# Gas_Sampler-5V_Buck.net
KiCad netlist of a schematic drawn in Altium Designer
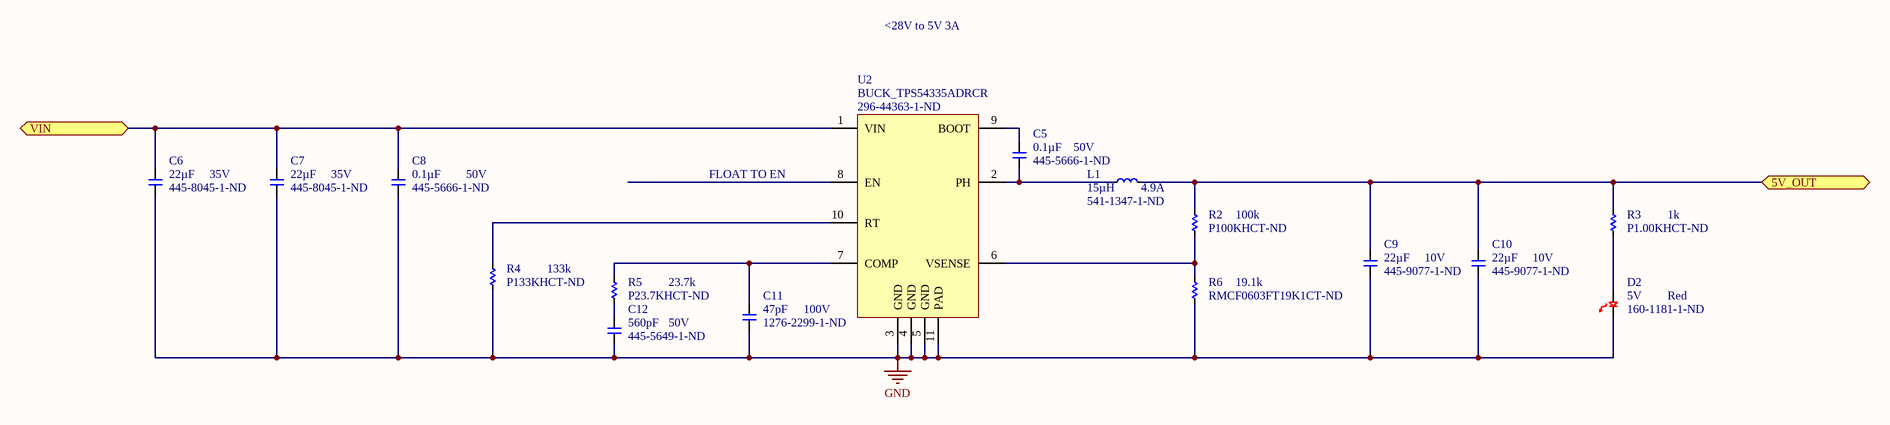
[diagram p0: Gas_Sampler-5V_Buck.SchDoc]

(export (version "E")
  (design (tool "Eeschema 10.0.6"))
  (components
    (comp (ref "C5")
      (value "0.1µF")
      (footprint "C0603")
      (description "CAP CER 0.1UF 50V 10% X7R 0603")
      (fields
        (field (name "MANUFACTURER") "TDK Corporation")
        (field (name "MANUFACTURER PART NUMBER") "CGA3E2X7R1H104K080AA")
        (field (name "VOLTAGE - RATED") "50V")
        (field (name "SUPPLIER PART NUMBER 1") "445-5666-1-ND")
      )
      (libsource (lib "capacitor") (part "CAP_CER_0603_0.1UF_50V_10%_X7R"))
    )
    (comp (ref "C6")
      (value "22µF")
      (footprint "C1206")
      (description "CAP CER 22UF 35V X5R 1206")
      (fields
        (field (name "MANUFACTURER") "TDK Corporation")
        (field (name "MANUFACTURER PART NUMBER") "C3216X5R1V226M160AC")
        (field (name "VOLTAGE - RATED") "35V")
        (field (name "SUPPLIER PART NUMBER 1") "445-8045-1-ND")
      )
      (libsource (lib "capacitor") (part "CAP_CER_1206_22UF_35V_20%_X5R"))
    )
    (comp (ref "C7")
      (value "22µF")
      (footprint "C1206")
      (description "CAP CER 22UF 35V X5R 1206")
      (fields
        (field (name "MANUFACTURER") "TDK Corporation")
        (field (name "MANUFACTURER PART NUMBER") "C3216X5R1V226M160AC")
        (field (name "VOLTAGE - RATED") "35V")
        (field (name "SUPPLIER PART NUMBER 1") "445-8045-1-ND")
      )
      (libsource (lib "capacitor") (part "CAP_CER_1206_22UF_35V_20%_X5R"))
    )
    (comp (ref "C8")
      (value "0.1µF")
      (footprint "C0603")
      (description "CAP CER 0.1UF 50V 10% X7R 0603")
      (fields
        (field (name "MANUFACTURER") "TDK Corporation")
        (field (name "MANUFACTURER PART NUMBER") "CGA3E2X7R1H104K080AA")
        (field (name "VOLTAGE - RATED") "50V")
        (field (name "SUPPLIER PART NUMBER 1") "445-5666-1-ND")
      )
      (libsource (lib "capacitor") (part "CAP_CER_0603_0.1UF_50V_10%_X7R"))
    )
    (comp (ref "C9")
      (value "22µF")
      (footprint "C0603")
      (description "CAP CER 22UF 10V 20% X5R 0603")
      (fields
        (field (name "MANUFACTURER") "TDK Corporation")
        (field (name "MANUFACTURER PART NUMBER") "C1608X5R1A226M080AC")
        (field (name "SUPPLIER PART NUMBER 1") "445-9077-1-ND")
        (field (name "VOLTAGE - RATED") "10V")
      )
      (libsource (lib "capacitor") (part "CAP_CER_0603_22UF_10V_20%_X5R"))
    )
    (comp (ref "C10")
      (value "22µF")
      (footprint "C0603")
      (description "CAP CER 22UF 10V 20% X5R 0603")
      (fields
        (field (name "MANUFACTURER") "TDK Corporation")
        (field (name "MANUFACTURER PART NUMBER") "C1608X5R1A226M080AC")
        (field (name "SUPPLIER PART NUMBER 1") "445-9077-1-ND")
        (field (name "VOLTAGE - RATED") "10V")
      )
      (libsource (lib "capacitor") (part "CAP_CER_0603_22UF_10V_20%_X5R"))
    )
    (comp (ref "C11")
      (value "47pF")
      (footprint "C0603")
      (description "CAP CER 47PF 100V C0G/NP0 0603")
      (fields
        (field (name "MANUFACTURER") "Samsung Electro-Mechanics")
        (field (name "MANUFACTURER PART NUMBER") "CL10C470JC8NNNC")
        (field (name "VOLTAGE - RATED") "100V")
        (field (name "SUPPLIER PART NUMBER 1") "1276-2299-1-ND")
      )
      (libsource (lib "capacitor") (part "CAP_CER_0603_47PF_100V_5%_NP0"))
    )
    (comp (ref "C12")
      (value "560pF")
      (footprint "C0603")
      (description "CAP CER 560PF 50V 5% NP0 0603")
      (fields
        (field (name "MANUFACTURER") "TDK Corporation")
        (field (name "MANUFACTURER PART NUMBER") "CGA3E2C0G1H561J080AA")
        (field (name "SUPPLIER PART NUMBER 1") "445-5649-1-ND")
        (field (name "VOLTAGE - RATED") "50V")
      )
      (libsource (lib "capacitor") (part "CAP_CER_0603_560PF_50V_5%_NP0"))
    )
    (comp (ref "D2")
      (value "5V")
      (footprint "LED_0603_RED")
      (description "LED RED CLEAR 0603 SMD")
      (fields
        (field (name "MANUFACTURER") "Lite-On Inc")
        (field (name "MANUFACTURER PART NUMBER") "LTST-C190CKT")
        (field (name "SUPPLIER PART NUMBER 1") "160-1181-1-ND")
        (field (name "COLOR") "Red")
      )
      (libsource (lib "diode") (part "LED_0603_RED_LR_LTST-C190CKT"))
    )
    (comp (ref "L1")
      (value "15µH")
      (footprint "INDUCTOR_IHLP3232_4MM_HEIGHT")
      (description "INDUCTOR POWER 15UH 4.9A SMD")
      (fields
        (field (name "MANUFACTURER") "Vishay Dale")
        (field (name "MANUFACTURER PART NUMBER") "IHLP3232DZER150M11")
        (field (name "CURRENT RATING") "4.9A")
        (field (name "SUPPLIER PART NUMBER 1") "541-1347-1-ND")
      )
      (libsource (lib "inductor") (part "IND_15UH_4.9A_IHLP3232DZER150M11"))
    )
    (comp (ref "R2")
      (value "100k")
      (footprint "R0603")
      (description "RES 100K OHM 1/10W 1% 0603 SMD")
      (fields
        (field (name "MANUFACTURER") "Panasonic Electronic Components")
        (field (name "MANUFACTURER PART NUMBER") "ERJ-3EKF1003V")
        (field (name "SUPPLIER PART NUMBER 1") "P100KHCT-ND")
      )
      (libsource (lib "resistor") (part "RES_0603_100K_OHM_1/10W_1%"))
    )
    (comp (ref "R3")
      (value "1k")
      (footprint "R0603")
      (description "RES 1K OHM 1/10W 1% 0603 SMD")
      (fields
        (field (name "MANUFACTURER") "Panasonic Electronic Components")
        (field (name "MANUFACTURER PART NUMBER") "ERJ-3EKF1001V")
        (field (name "SUPPLIER PART NUMBER 1") "P1.00KHCT-ND")
      )
      (libsource (lib "resistor") (part "RES_0603_1K_OHM_1/10W_1%"))
    )
    (comp (ref "R4")
      (value "133k")
      (footprint "R0603")
      (description "RES 133K OHM 1% 1/10W 0603")
      (fields
        (field (name "MANUFACTURER") "Panasonic Electronic Components")
        (field (name "TOLERANCE") "±1%")
        (field (name "SUPPLIER PART NUMBER 1") "P133KHCT-ND")
      )
      (libsource (lib "resistor") (part "RES_0603_133K_OHM_1/10W_1%"))
    )
    (comp (ref "R5")
      (value "23.7k")
      (footprint "R0603")
      (description "RES 23.7K OHM 1% 1/10W 0603")
      (fields
        (field (name "MANUFACTURER") "Panasonic Electronic Components")
        (field (name "MANUFACTURER PART NUMBER") "ERJ-3EKF2372V")
        (field (name "SUPPLIER PART NUMBER 1") "P23.7KHCT-ND")
      )
      (libsource (lib "resistor") (part "RES_0603_23.7K_OHMS_1/10W_1%"))
    )
    (comp (ref "R6")
      (value "19.1k")
      (footprint "R0603")
      (description "RES 19.1K OHM 1% 1/10W 0603")
      (fields
        (field (name "MANUFACTURER") "Stackpole Electronics Inc")
        (field (name "TOLERANCE") "±1%")
        (field (name "SUPPLIER PART NUMBER 1") "RMCF0603FT19K1CT-ND")
      )
      (libsource (lib "resistor") (part "RES_0603_19.1K_OHM_1/10W_1%"))
    )
    (comp (ref "U2")
      (value "BUCK_TPS54335ADRCR")
      (footprint "PVSON50P300X300X70-10N")
      (description "IC REG BUCK ADJUSTABLE 3A 10VSON")
      (fields
        (field (name "MANUFACTURER") "Texas Instruments")
        (field (name "MANUFACTURER PART NUMBER") "TPS54335ADRCR")
        (field (name "SUPPLIER PART NUMBER 1") "296-44363-1-ND")
      )
      (libsource (lib "ic_pmic") (part "BUCK_TPS54335ADRCR"))
    )
  )
  (nets
    (net (code "1") (name "/5V_OUT") (class "Default")
      (node (ref "C10") (pin "1") (pintype "passive"))
      (node (ref "C9") (pin "1") (pintype "passive"))
      (node (ref "L1") (pin "2") (pintype "passive"))
      (node (ref "R2") (pin "2") (pintype "passive"))
      (node (ref "R3") (pin "2") (pintype "passive"))
    )
    (net (code "2") (name "/VIN") (class "Default")
      (node (ref "C6") (pin "1") (pintype "passive"))
      (node (ref "C7") (pin "1") (pintype "passive"))
      (node (ref "C8") (pin "1") (pintype "passive"))
      (node (ref "U2") (pin "1") (pinfunction "VIN_1") (pintype "passive"))
    )
    (net (code "3") (name "GND") (class "Default")
      (node (ref "C10") (pin "2") (pintype "passive"))
      (node (ref "C11") (pin "2") (pintype "passive"))
      (node (ref "C12") (pin "2") (pintype "passive"))
      (node (ref "C6") (pin "2") (pintype "passive"))
      (node (ref "C7") (pin "2") (pintype "passive"))
      (node (ref "C8") (pin "2") (pintype "passive"))
      (node (ref "C9") (pin "2") (pintype "passive"))
      (node (ref "D2") (pin "2") (pinfunction "CATHODE_2") (pintype "passive"))
      (node (ref "R4") (pin "1") (pintype "passive"))
      (node (ref "R6") (pin "1") (pintype "passive"))
      (node (ref "U2") (pin "11") (pinfunction "PAD_11") (pintype "passive"))
      (node (ref "U2") (pin "3") (pinfunction "GND_3") (pintype "passive"))
      (node (ref "U2") (pin "4") (pinfunction "GND_4") (pintype "passive"))
      (node (ref "U2") (pin "5") (pinfunction "GND_5") (pintype "passive"))
    )
    (net (code "4") (name "Net-(C12-Pad1)") (class "Default")
      (node (ref "C12") (pin "1") (pintype "passive"))
      (node (ref "R5") (pin "1") (pintype "passive"))
    )
    (net (code "5") (name "Net-(D2-ANODE)") (class "Default")
      (node (ref "D2") (pin "1") (pinfunction "ANODE_1") (pintype "passive"))
      (node (ref "R3") (pin "1") (pintype "passive"))
    )
    (net (code "6") (name "Net-(U2-BOOT)") (class "Default")
      (node (ref "C5") (pin "1") (pintype "passive"))
      (node (ref "U2") (pin "9") (pinfunction "BOOT_9") (pintype "passive"))
    )
    (net (code "7") (name "Net-(U2-COMP)") (class "Default")
      (node (ref "C11") (pin "1") (pintype "passive"))
      (node (ref "R5") (pin "2") (pintype "passive"))
      (node (ref "U2") (pin "7") (pinfunction "COMP_7") (pintype "passive"))
    )
    (net (code "8") (name "Net-(U2-PH)") (class "Default")
      (node (ref "C5") (pin "2") (pintype "passive"))
      (node (ref "L1") (pin "1") (pintype "passive"))
      (node (ref "U2") (pin "2") (pinfunction "PH_2") (pintype "passive"))
    )
    (net (code "9") (name "Net-(U2-RT)") (class "Default")
      (node (ref "R4") (pin "2") (pintype "passive"))
      (node (ref "U2") (pin "10") (pinfunction "RT_10") (pintype "passive"))
    )
    (net (code "10") (name "Net-(U2-VSENSE)") (class "Default")
      (node (ref "R2") (pin "1") (pintype "passive"))
      (node (ref "R6") (pin "2") (pintype "passive"))
      (node (ref "U2") (pin "6") (pinfunction "VSENSE_6") (pintype "passive"))
    )
    (net (code "11") (name "unconnected-(U2-EN-Pad8)") (class "Default")
      (node (ref "U2") (pin "8") (pinfunction "EN_8") (pintype "passive"))
    )
  )
)
